# BatteryBalancer.net
KiCad netlist of a schematic drawn in EAGLE
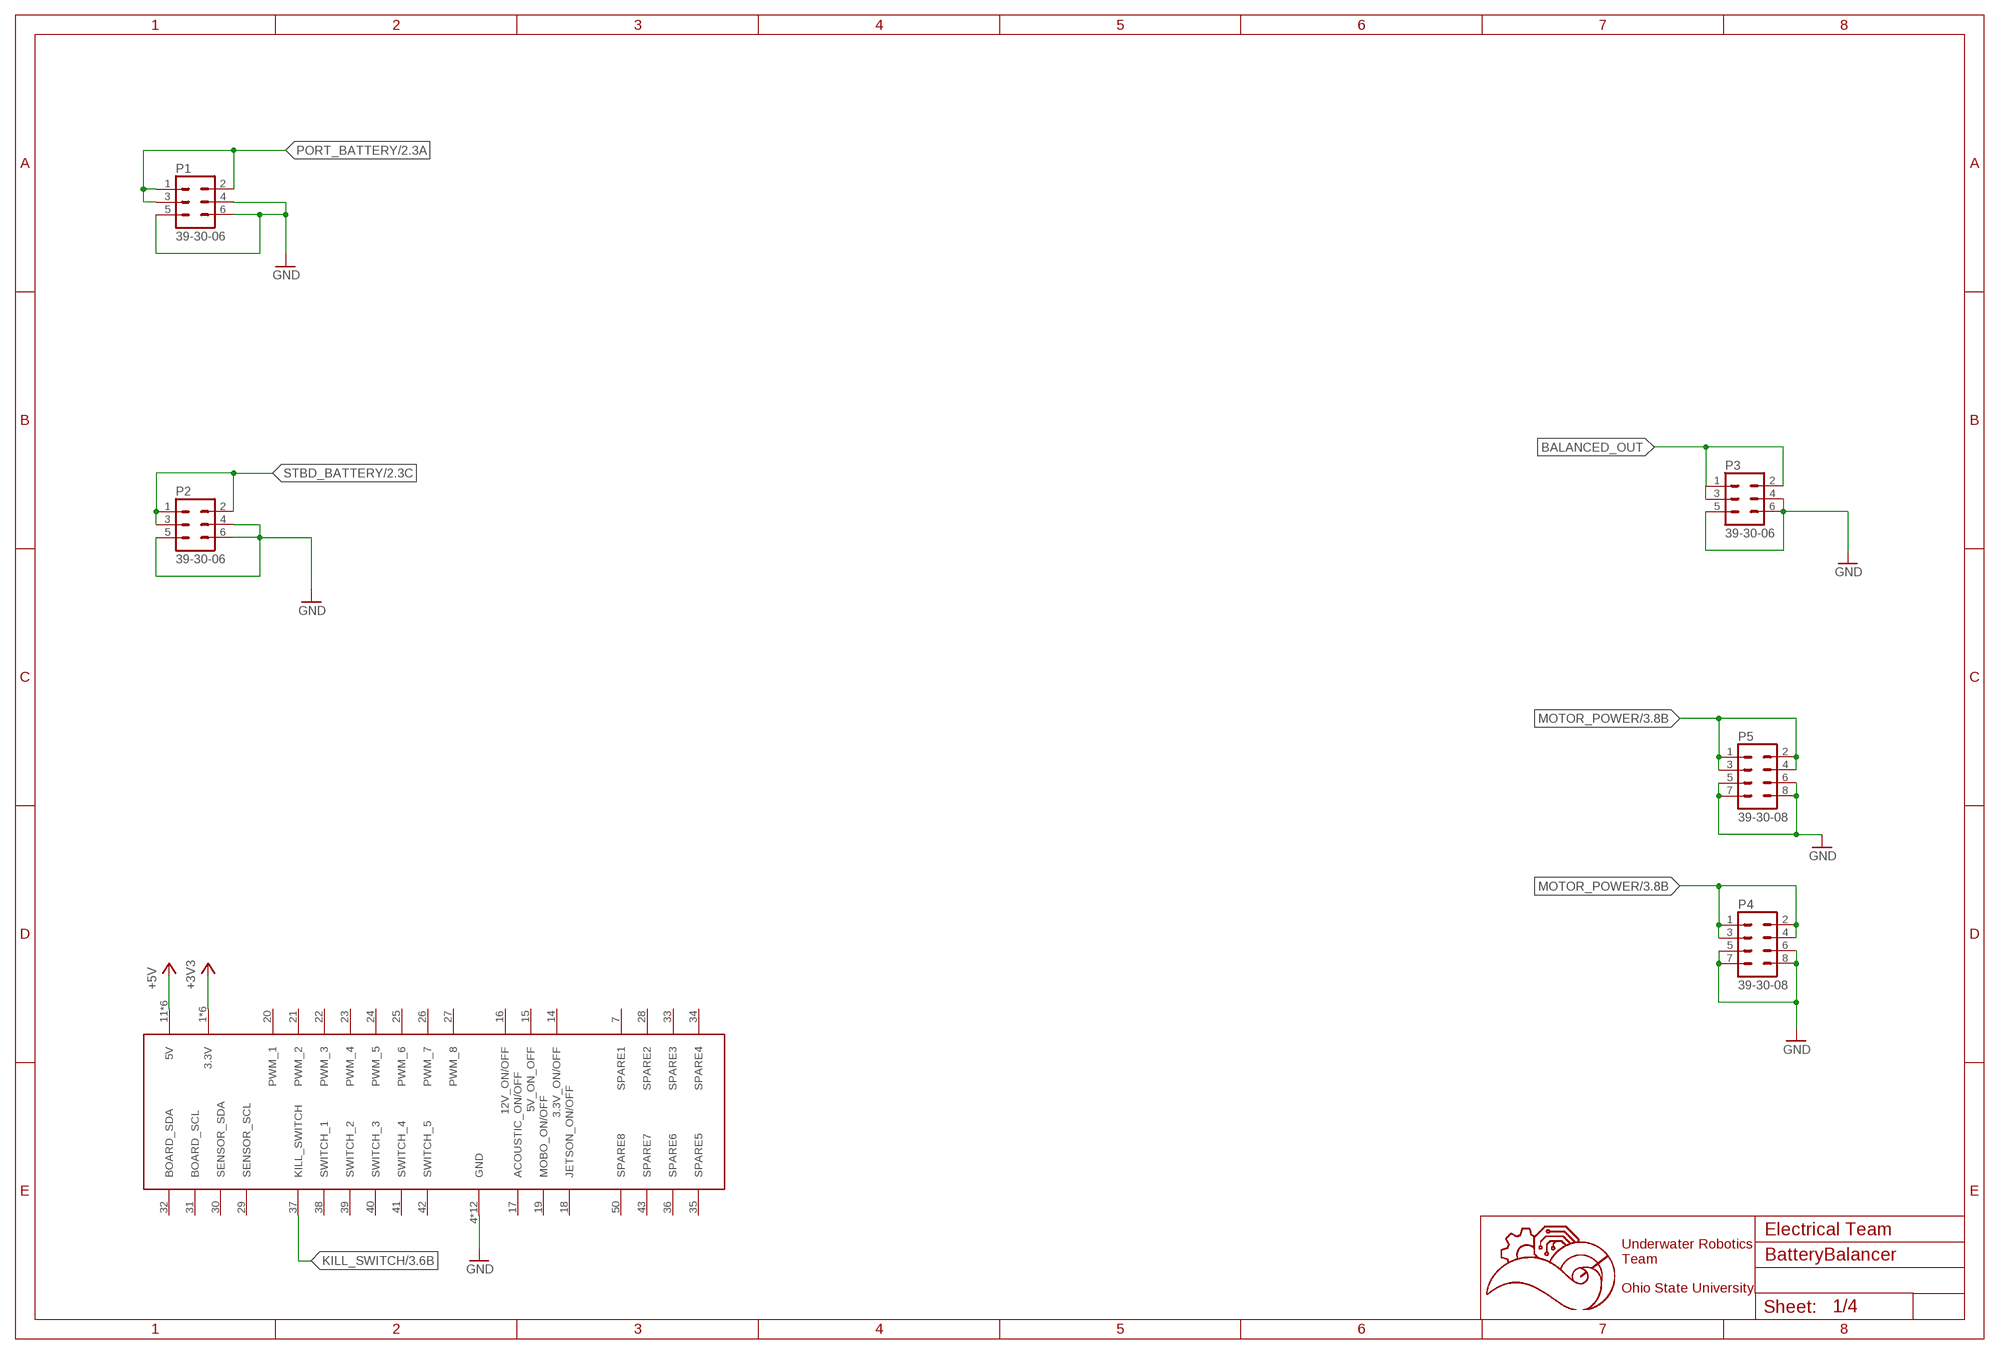
[diagram p0: schematic, sheet 1]
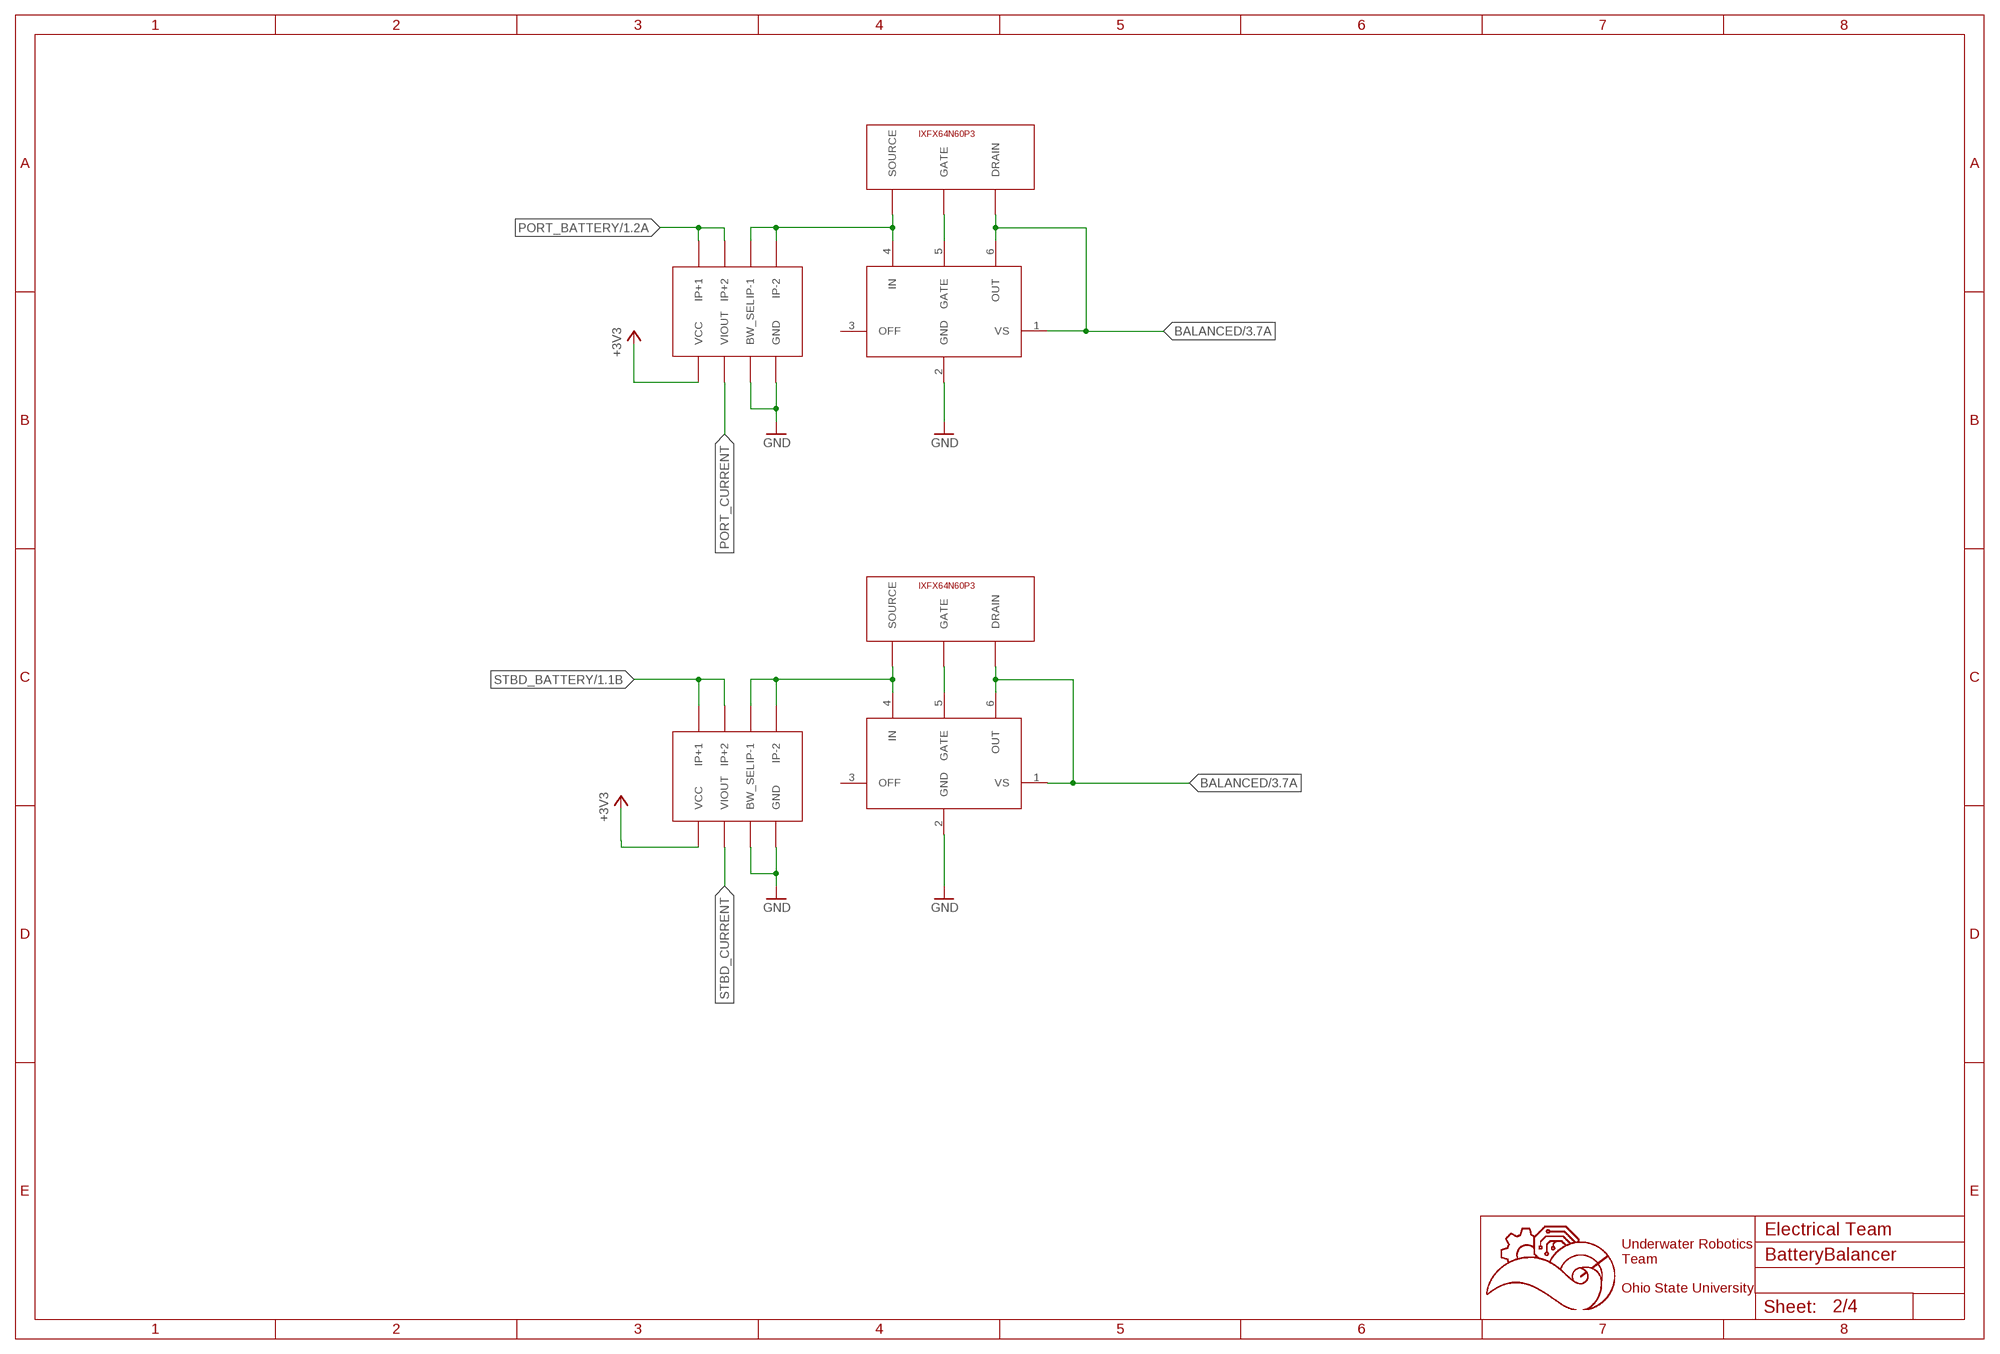
[diagram p1: schematic, sheet 2]
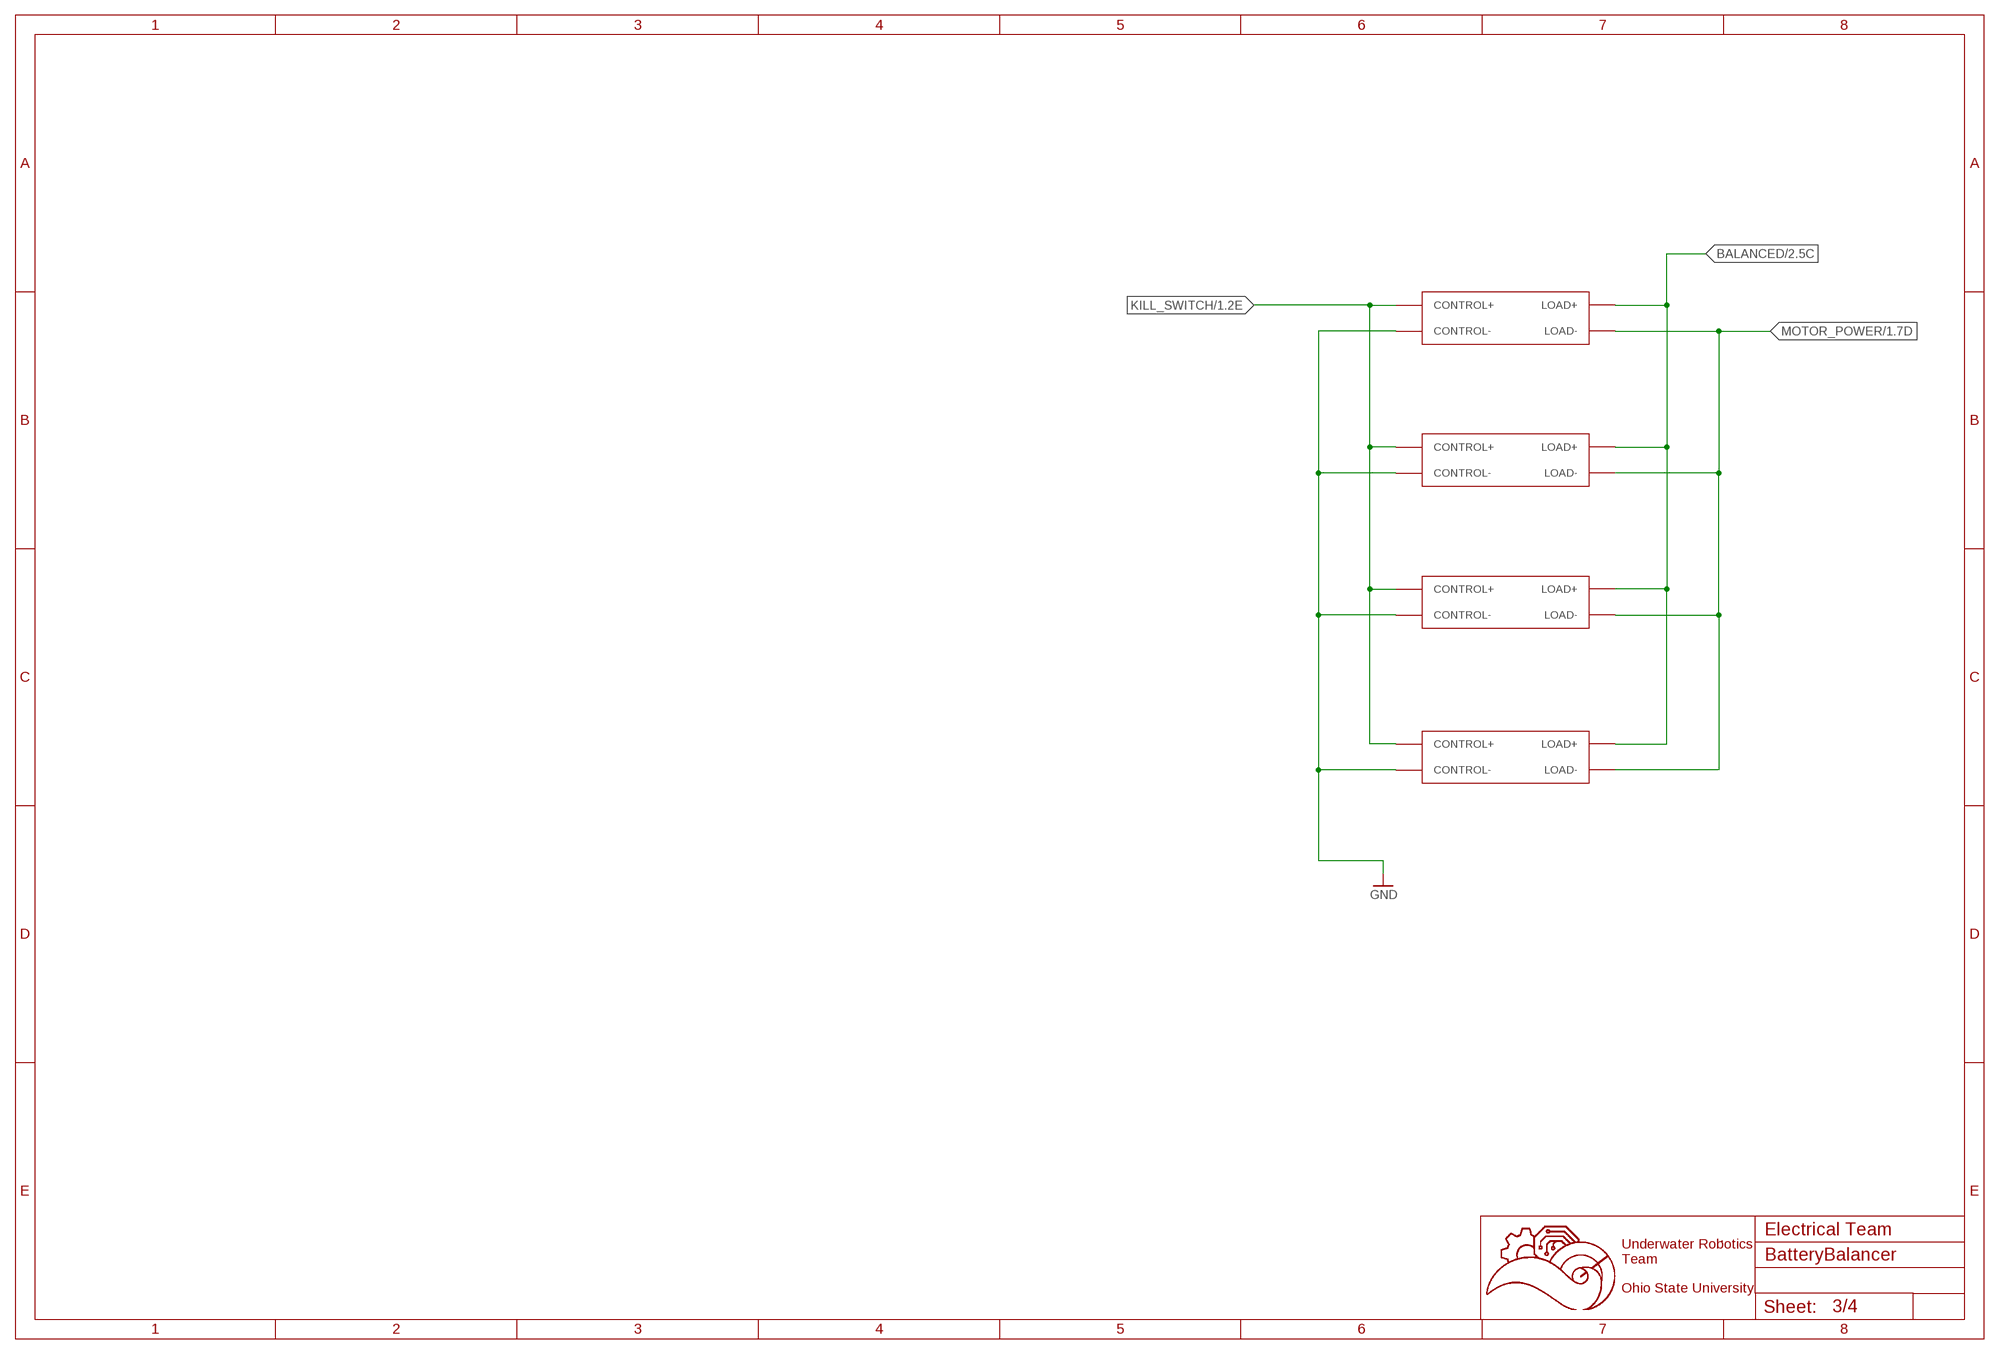
[diagram p2: schematic, sheet 3]
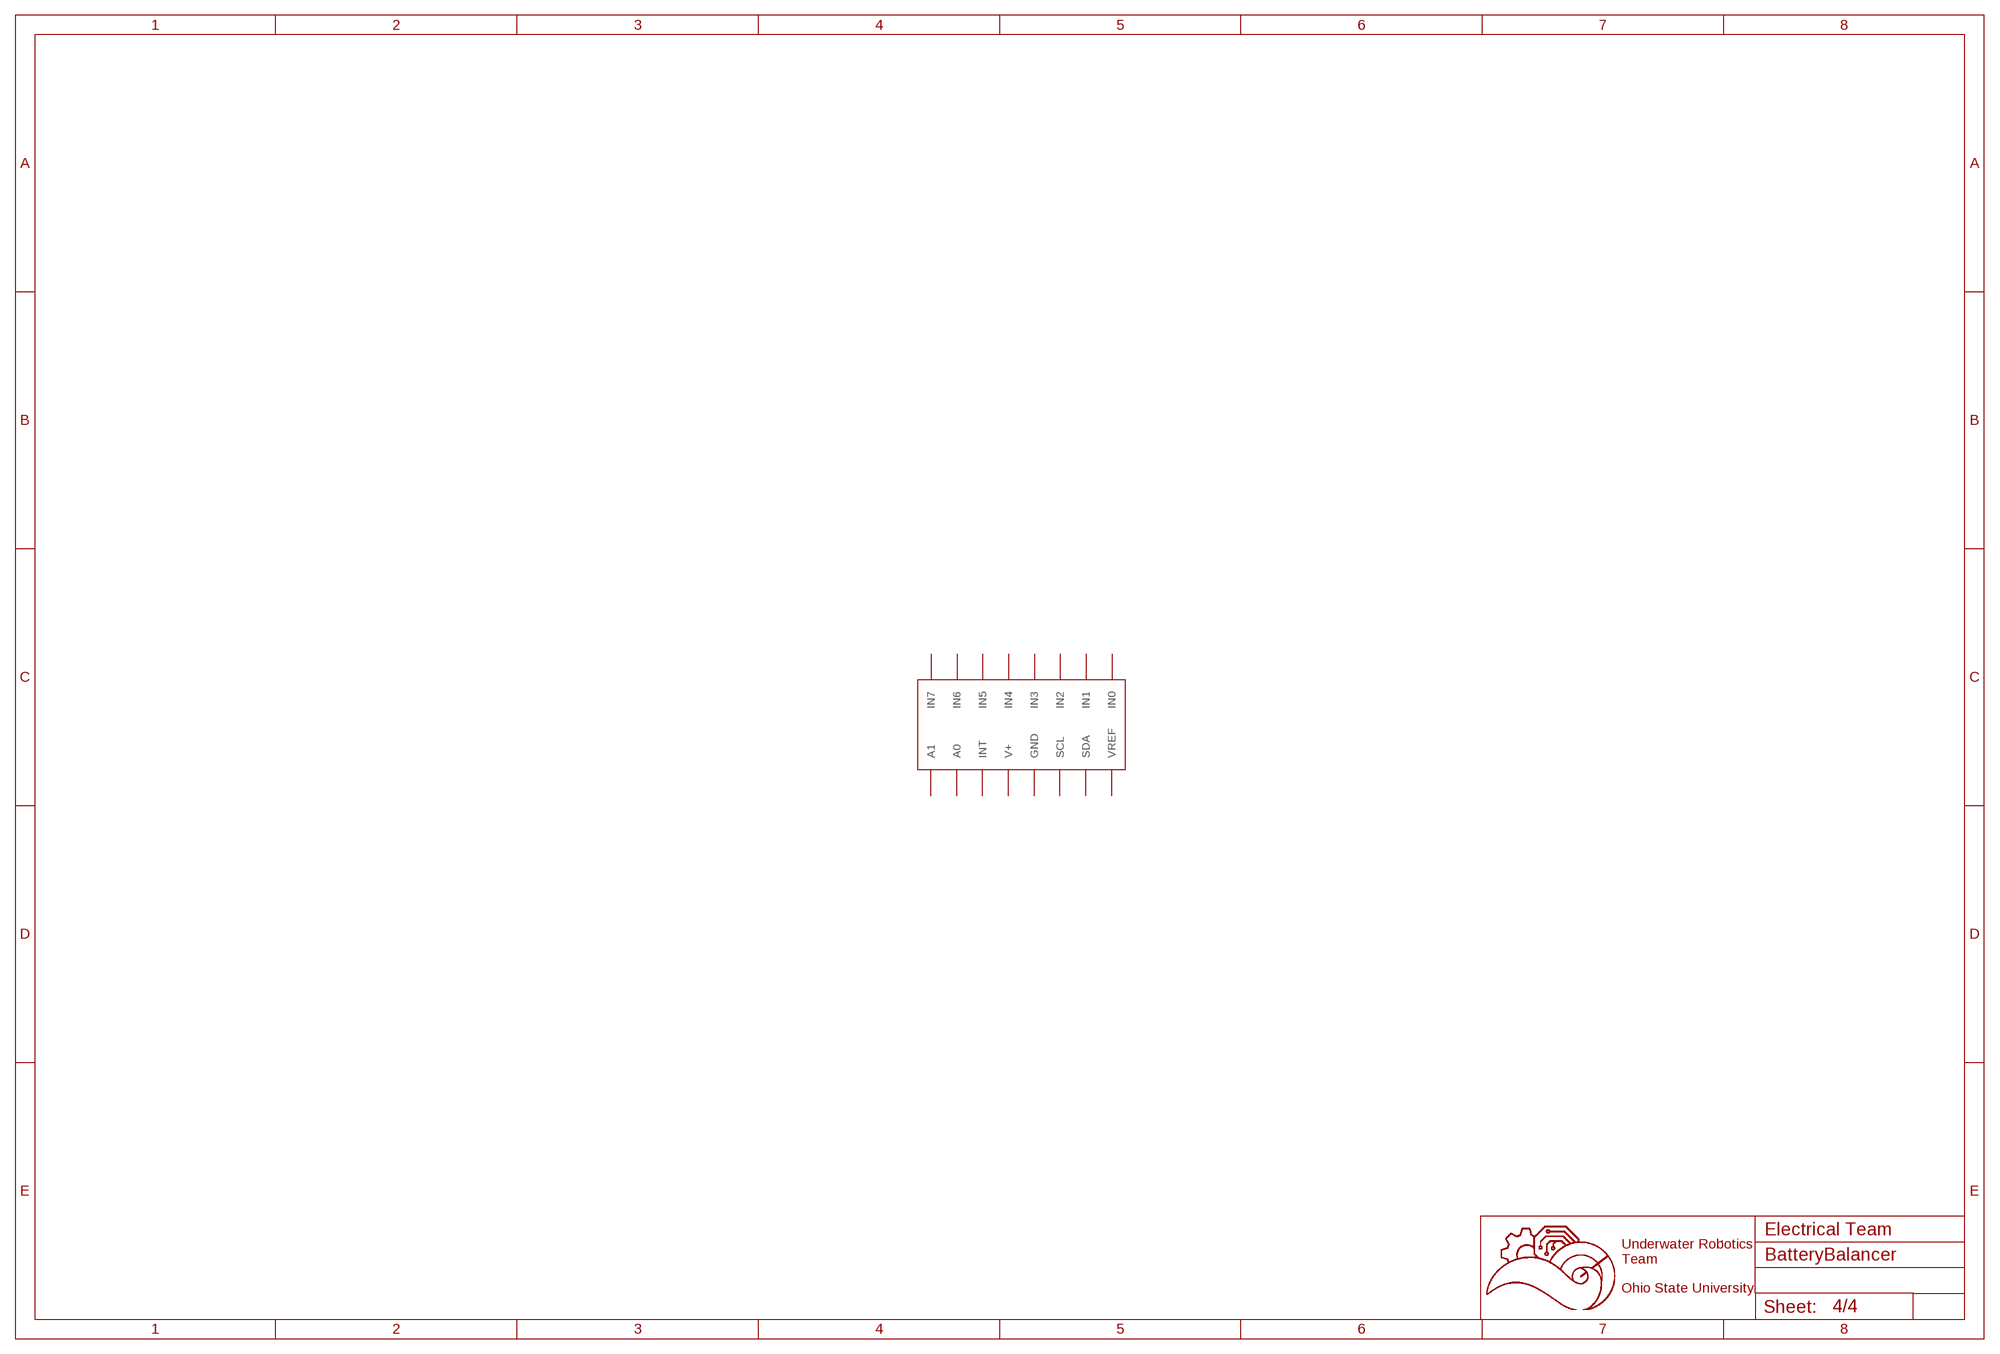
[diagram p3: schematic, sheet 4]

(export (version "E")
  (design (tool "Eeschema 10.0.6"))
  (components
    (comp (ref "U$12")
      (value "ADC128D818")
      (footprint "eagle-import:TSSOP-16")
      (libsource (lib "eagle-import") (part "ADC128D818"))
    )
    (comp (ref "U$8")
      (value "CMX60D20")
      (footprint "eagle-import:CMX60D20")
      (libsource (lib "eagle-import") (part "CMX60D20"))
    )
    (comp (ref "U$9")
      (value "CMX60D20")
      (footprint "eagle-import:CMX60D20")
      (libsource (lib "eagle-import") (part "CMX60D20"))
    )
    (comp (ref "U$10")
      (value "CMX60D20")
      (footprint "eagle-import:CMX60D20")
      (libsource (lib "eagle-import") (part "CMX60D20"))
    )
    (comp (ref "U$11")
      (value "CMX60D20")
      (footprint "eagle-import:CMX60D20")
      (libsource (lib "eagle-import") (part "CMX60D20"))
    )
    (comp (ref "U$2")
      (value "LM5050")
      (footprint "eagle-import:LM5050")
      (libsource (lib "eagle-import") (part "LM5050"))
    )
    (comp (ref "U$3")
      (value "LM5050")
      (footprint "eagle-import:LM5050")
      (libsource (lib "eagle-import") (part "LM5050"))
    )
    (comp (ref "U$4")
      (value "IXFX64N60P3")
      (footprint "eagle-import:IXFX64N60P3")
      (libsource (lib "eagle-import") (part "IXFX64N60P3"))
    )
    (comp (ref "U$5")
      (value "IXFX64N60P3")
      (footprint "eagle-import:IXFX64N60P3")
      (libsource (lib "eagle-import") (part "IXFX64N60P3"))
    )
    (comp (ref "U$6")
      (value "ACS722")
      (footprint "eagle-import:SOIC-8")
      (libsource (lib "eagle-import") (part "ACS722"))
    )
    (comp (ref "U$7")
      (value "ACS722")
      (footprint "eagle-import:SOIC-8")
      (libsource (lib "eagle-import") (part "ACS722"))
    )
    (comp (ref "P1")
      (value "39-30-06")
      (footprint "eagle-import:39-30-_06_")
      (libsource (lib "eagle-import") (part "39-30-?06?"))
    )
    (comp (ref "P2")
      (value "39-30-06")
      (footprint "eagle-import:39-30-_06_")
      (libsource (lib "eagle-import") (part "39-30-?06?"))
    )
    (comp (ref "P3")
      (value "39-30-06")
      (footprint "eagle-import:39-30-_06_")
      (libsource (lib "eagle-import") (part "39-30-?06?"))
    )
    (comp (ref "P4")
      (value "39-30-08")
      (footprint "eagle-import:39-30-_08_")
      (libsource (lib "eagle-import") (part "39-30-?08?"))
    )
    (comp (ref "P5")
      (value "39-30-08")
      (footprint "eagle-import:39-30-_08_")
      (libsource (lib "eagle-import") (part "39-30-?08?"))
    )
    (comp (ref "U$1")
      (value "5530843-EDGE")
      (footprint "eagle-import:5530843-6-BOARDFINGERS")
      (libsource (lib "eagle-import") (part "5530843-EDGE"))
    )
  )
  (nets
    (net (code "1") (name "+3V3") (class "Default")
      (node (ref "U$1") (pin "1") (pinfunction "3.3V_1") (pintype "bidirectional"))
      (node (ref "U$1") (pin "2") (pinfunction "3.3V_2") (pintype "bidirectional"))
      (node (ref "U$1") (pin "3") (pinfunction "3.3V_3") (pintype "bidirectional"))
      (node (ref "U$1") (pin "54") (pinfunction "3.3V_54") (pintype "bidirectional"))
      (node (ref "U$1") (pin "55") (pinfunction "3.3V_55") (pintype "bidirectional"))
      (node (ref "U$1") (pin "56") (pinfunction "3.3V_56") (pintype "bidirectional"))
      (node (ref "U$6") (pin "VCC") (pinfunction "VCC_VCC") (pintype "bidirectional"))
      (node (ref "U$7") (pin "VCC") (pinfunction "VCC_VCC") (pintype "bidirectional"))
    )
    (net (code "2") (name "+5V") (class "Default")
      (node (ref "U$1") (pin "11") (pinfunction "5V_11") (pintype "bidirectional"))
      (node (ref "U$1") (pin "12") (pinfunction "5V_12") (pintype "bidirectional"))
      (node (ref "U$1") (pin "13") (pinfunction "5V_13") (pintype "bidirectional"))
      (node (ref "U$1") (pin "44") (pinfunction "5V_44") (pintype "bidirectional"))
      (node (ref "U$1") (pin "45") (pinfunction "5V_45") (pintype "bidirectional"))
      (node (ref "U$1") (pin "46") (pinfunction "5V_46") (pintype "bidirectional"))
    )
    (net (code "3") (name "BALANCED") (class "Default")
      (node (ref "U$10") (pin "LOAD+") (pinfunction "LOAD+_LOAD+") (pintype "bidirectional"))
      (node (ref "U$11") (pin "LOAD+") (pinfunction "LOAD+_LOAD+") (pintype "bidirectional"))
      (node (ref "U$2") (pin "1") (pinfunction "VS_1") (pintype "bidirectional"))
      (node (ref "U$2") (pin "6") (pinfunction "OUT_6") (pintype "bidirectional"))
      (node (ref "U$3") (pin "1") (pinfunction "VS_1") (pintype "bidirectional"))
      (node (ref "U$3") (pin "6") (pinfunction "OUT_6") (pintype "bidirectional"))
      (node (ref "U$4") (pin "DRAIN") (pinfunction "DRAIN_DRAIN") (pintype "bidirectional"))
      (node (ref "U$5") (pin "DRAIN") (pinfunction "DRAIN_DRAIN") (pintype "bidirectional"))
      (node (ref "U$8") (pin "LOAD+") (pinfunction "LOAD+_LOAD+") (pintype "bidirectional"))
      (node (ref "U$9") (pin "LOAD+") (pinfunction "LOAD+_LOAD+") (pintype "bidirectional"))
    )
    (net (code "4") (name "BALANCED_OUT") (class "Default")
      (node (ref "P3") (pin "1") (pinfunction "1_1") (pintype "passive"))
      (node (ref "P3") (pin "2") (pinfunction "2_2") (pintype "passive"))
      (node (ref "P3") (pin "3") (pinfunction "3_3") (pintype "passive"))
    )
    (net (code "5") (name "GND") (class "Default")
      (node (ref "P1") (pin "4") (pinfunction "4_4") (pintype "passive"))
      (node (ref "P1") (pin "5") (pinfunction "5_5") (pintype "passive"))
      (node (ref "P1") (pin "6") (pinfunction "6_6") (pintype "passive"))
      (node (ref "P2") (pin "4") (pinfunction "4_4") (pintype "passive"))
      (node (ref "P2") (pin "5") (pinfunction "5_5") (pintype "passive"))
      (node (ref "P2") (pin "6") (pinfunction "6_6") (pintype "passive"))
      (node (ref "P3") (pin "4") (pinfunction "4_4") (pintype "passive"))
      (node (ref "P3") (pin "5") (pinfunction "5_5") (pintype "passive"))
      (node (ref "P3") (pin "6") (pinfunction "6_6") (pintype "passive"))
      (node (ref "P4") (pin "5") (pinfunction "5_5") (pintype "passive"))
      (node (ref "P4") (pin "6") (pinfunction "6_6") (pintype "passive"))
      (node (ref "P4") (pin "7") (pinfunction "7_7") (pintype "passive"))
      (node (ref "P4") (pin "8") (pinfunction "8_8") (pintype "passive"))
      (node (ref "P5") (pin "5") (pinfunction "5_5") (pintype "passive"))
      (node (ref "P5") (pin "6") (pinfunction "6_6") (pintype "passive"))
      (node (ref "P5") (pin "7") (pinfunction "7_7") (pintype "passive"))
      (node (ref "P5") (pin "8") (pinfunction "8_8") (pintype "passive"))
      (node (ref "U$1") (pin "10") (pinfunction "GND_10") (pintype "bidirectional"))
      (node (ref "U$1") (pin "4") (pinfunction "GND_4") (pintype "bidirectional"))
      (node (ref "U$1") (pin "47") (pinfunction "GND_47") (pintype "bidirectional"))
      (node (ref "U$1") (pin "48") (pinfunction "GND_48") (pintype "bidirectional"))
      (node (ref "U$1") (pin "49") (pinfunction "GND_49") (pintype "bidirectional"))
      (node (ref "U$1") (pin "5") (pinfunction "GND_5") (pintype "bidirectional"))
      (node (ref "U$1") (pin "51") (pinfunction "GND_51") (pintype "bidirectional"))
      (node (ref "U$1") (pin "52") (pinfunction "GND_52") (pintype "bidirectional"))
      (node (ref "U$1") (pin "53") (pinfunction "GND_53") (pintype "bidirectional"))
      (node (ref "U$1") (pin "6") (pinfunction "GND_6") (pintype "bidirectional"))
      (node (ref "U$1") (pin "8") (pinfunction "GND_8") (pintype "bidirectional"))
      (node (ref "U$1") (pin "9") (pinfunction "GND_9") (pintype "bidirectional"))
      (node (ref "U$10") (pin "CONTROL-") (pinfunction "CONTROL-_CONTROL-") (pintype "bidirectional"))
      (node (ref "U$11") (pin "CONTROL-") (pinfunction "CONTROL-_CONTROL-") (pintype "bidirectional"))
      (node (ref "U$2") (pin "2") (pinfunction "GND_2") (pintype "bidirectional"))
      (node (ref "U$3") (pin "2") (pinfunction "GND_2") (pintype "bidirectional"))
      (node (ref "U$6") (pin "BW_SEL") (pinfunction "BW_SEL_BW_SEL") (pintype "bidirectional"))
      (node (ref "U$6") (pin "GND") (pinfunction "GND_GND") (pintype "bidirectional"))
      (node (ref "U$7") (pin "BW_SEL") (pinfunction "BW_SEL_BW_SEL") (pintype "bidirectional"))
      (node (ref "U$7") (pin "GND") (pinfunction "GND_GND") (pintype "bidirectional"))
      (node (ref "U$8") (pin "CONTROL-") (pinfunction "CONTROL-_CONTROL-") (pintype "bidirectional"))
      (node (ref "U$9") (pin "CONTROL-") (pinfunction "CONTROL-_CONTROL-") (pintype "bidirectional"))
    )
    (net (code "6") (name "KILL_SWITCH") (class "Default")
      (node (ref "U$1") (pin "37") (pinfunction "KILL_SWITCH_37") (pintype "output"))
      (node (ref "U$10") (pin "CONTROL+") (pinfunction "CONTROL+_CONTROL+") (pintype "bidirectional"))
      (node (ref "U$11") (pin "CONTROL+") (pinfunction "CONTROL+_CONTROL+") (pintype "bidirectional"))
      (node (ref "U$8") (pin "CONTROL+") (pinfunction "CONTROL+_CONTROL+") (pintype "bidirectional"))
      (node (ref "U$9") (pin "CONTROL+") (pinfunction "CONTROL+_CONTROL+") (pintype "bidirectional"))
    )
    (net (code "7") (name "MOTOR_POWER") (class "Default")
      (node (ref "P4") (pin "1") (pinfunction "1_1") (pintype "passive"))
      (node (ref "P4") (pin "2") (pinfunction "2_2") (pintype "passive"))
      (node (ref "P4") (pin "3") (pinfunction "3_3") (pintype "passive"))
      (node (ref "P4") (pin "4") (pinfunction "4_4") (pintype "passive"))
      (node (ref "P5") (pin "1") (pinfunction "1_1") (pintype "passive"))
      (node (ref "P5") (pin "2") (pinfunction "2_2") (pintype "passive"))
      (node (ref "P5") (pin "3") (pinfunction "3_3") (pintype "passive"))
      (node (ref "P5") (pin "4") (pinfunction "4_4") (pintype "passive"))
      (node (ref "U$10") (pin "LOAD-") (pinfunction "LOAD-_LOAD-") (pintype "bidirectional"))
      (node (ref "U$11") (pin "LOAD-") (pinfunction "LOAD-_LOAD-") (pintype "bidirectional"))
      (node (ref "U$8") (pin "LOAD-") (pinfunction "LOAD-_LOAD-") (pintype "bidirectional"))
      (node (ref "U$9") (pin "LOAD-") (pinfunction "LOAD-_LOAD-") (pintype "bidirectional"))
    )
    (net (code "8") (name "Net-(U$2-GATE)") (class "Default")
      (node (ref "U$2") (pin "5") (pinfunction "GATE_5") (pintype "bidirectional"))
      (node (ref "U$4") (pin "GATE") (pinfunction "GATE_GATE") (pintype "bidirectional"))
    )
    (net (code "9") (name "Net-(U$2-IN)") (class "Default")
      (node (ref "U$2") (pin "4") (pinfunction "IN_4") (pintype "bidirectional"))
      (node (ref "U$4") (pin "SOURCE") (pinfunction "SOURCE_SOURCE") (pintype "bidirectional"))
      (node (ref "U$6") (pin "IP-1") (pinfunction "IP-1_IP-1") (pintype "bidirectional"))
      (node (ref "U$6") (pin "IP-2") (pinfunction "IP-2_IP-2") (pintype "bidirectional"))
    )
    (net (code "10") (name "Net-(U$3-GATE)") (class "Default")
      (node (ref "U$3") (pin "5") (pinfunction "GATE_5") (pintype "bidirectional"))
      (node (ref "U$5") (pin "GATE") (pinfunction "GATE_GATE") (pintype "bidirectional"))
    )
    (net (code "11") (name "Net-(U$3-IN)") (class "Default")
      (node (ref "U$3") (pin "4") (pinfunction "IN_4") (pintype "bidirectional"))
      (node (ref "U$5") (pin "SOURCE") (pinfunction "SOURCE_SOURCE") (pintype "bidirectional"))
      (node (ref "U$7") (pin "IP-1") (pinfunction "IP-1_IP-1") (pintype "bidirectional"))
      (node (ref "U$7") (pin "IP-2") (pinfunction "IP-2_IP-2") (pintype "bidirectional"))
    )
    (net (code "12") (name "PORT_BATTERY") (class "Default")
      (node (ref "P1") (pin "1") (pinfunction "1_1") (pintype "passive"))
      (node (ref "P1") (pin "2") (pinfunction "2_2") (pintype "passive"))
      (node (ref "P1") (pin "3") (pinfunction "3_3") (pintype "passive"))
      (node (ref "U$6") (pin "IP+1") (pinfunction "IP+1_IP+1") (pintype "bidirectional"))
      (node (ref "U$6") (pin "IP+2") (pinfunction "IP+2_IP+2") (pintype "bidirectional"))
    )
    (net (code "13") (name "PORT_CURRENT") (class "Default")
      (node (ref "U$6") (pin "VIOUT") (pinfunction "VIOUT_VIOUT") (pintype "bidirectional"))
    )
    (net (code "14") (name "STBD_BATTERY") (class "Default")
      (node (ref "P2") (pin "1") (pinfunction "1_1") (pintype "passive"))
      (node (ref "P2") (pin "2") (pinfunction "2_2") (pintype "passive"))
      (node (ref "P2") (pin "3") (pinfunction "3_3") (pintype "passive"))
      (node (ref "U$7") (pin "IP+1") (pinfunction "IP+1_IP+1") (pintype "bidirectional"))
      (node (ref "U$7") (pin "IP+2") (pinfunction "IP+2_IP+2") (pintype "bidirectional"))
    )
    (net (code "15") (name "STBD_CURRENT") (class "Default")
      (node (ref "U$7") (pin "VIOUT") (pinfunction "VIOUT_VIOUT") (pintype "bidirectional"))
    )
    (net (code "16") (name "unconnected-(U$1-3.3V_ON{slash}OFF-Pad14)") (class "Default")
      (node (ref "U$1") (pin "14") (pinfunction "3.3V_ON/OFF_14") (pintype "bidirectional"))
    )
    (net (code "17") (name "unconnected-(U$1-5V_ON_OFF-Pad15)") (class "Default")
      (node (ref "U$1") (pin "15") (pinfunction "5V_ON_OFF_15") (pintype "bidirectional"))
    )
    (net (code "18") (name "unconnected-(U$1-12V_ON{slash}OFF-Pad16)") (class "Default")
      (node (ref "U$1") (pin "16") (pinfunction "12V_ON/OFF_16") (pintype "bidirectional"))
    )
    (net (code "19") (name "unconnected-(U$1-ACOUSTIC_ON{slash}OFF-Pad17)") (class "Default")
      (node (ref "U$1") (pin "17") (pinfunction "ACOUSTIC_ON/OFF_17") (pintype "bidirectional"))
    )
    (net (code "20") (name "unconnected-(U$1-BOARD_SCL-Pad31)") (class "Default")
      (node (ref "U$1") (pin "31") (pinfunction "BOARD_SCL_31") (pintype "bidirectional"))
    )
    (net (code "21") (name "unconnected-(U$1-BOARD_SDA-Pad32)") (class "Default")
      (node (ref "U$1") (pin "32") (pinfunction "BOARD_SDA_32") (pintype "bidirectional"))
    )
    (net (code "22") (name "unconnected-(U$1-JETSON_ON{slash}OFF-Pad18)") (class "Default")
      (node (ref "U$1") (pin "18") (pinfunction "JETSON_ON/OFF_18") (pintype "bidirectional"))
    )
    (net (code "23") (name "unconnected-(U$1-MOBO_ON{slash}OFF-Pad19)") (class "Default")
      (node (ref "U$1") (pin "19") (pinfunction "MOBO_ON/OFF_19") (pintype "bidirectional"))
    )
    (net (code "24") (name "unconnected-(U$1-PWM_1-Pad20)") (class "Default")
      (node (ref "U$1") (pin "20") (pinfunction "PWM_1_20") (pintype "bidirectional"))
    )
    (net (code "25") (name "unconnected-(U$1-PWM_2-Pad21)") (class "Default")
      (node (ref "U$1") (pin "21") (pinfunction "PWM_2_21") (pintype "bidirectional"))
    )
    (net (code "26") (name "unconnected-(U$1-PWM_3-Pad22)") (class "Default")
      (node (ref "U$1") (pin "22") (pinfunction "PWM_3_22") (pintype "bidirectional"))
    )
    (net (code "27") (name "unconnected-(U$1-PWM_4-Pad23)") (class "Default")
      (node (ref "U$1") (pin "23") (pinfunction "PWM_4_23") (pintype "bidirectional"))
    )
    (net (code "28") (name "unconnected-(U$1-PWM_5-Pad24)") (class "Default")
      (node (ref "U$1") (pin "24") (pinfunction "PWM_5_24") (pintype "bidirectional"))
    )
    (net (code "29") (name "unconnected-(U$1-PWM_6-Pad25)") (class "Default")
      (node (ref "U$1") (pin "25") (pinfunction "PWM_6_25") (pintype "bidirectional"))
    )
    (net (code "30") (name "unconnected-(U$1-PWM_7-Pad26)") (class "Default")
      (node (ref "U$1") (pin "26") (pinfunction "PWM_7_26") (pintype "bidirectional"))
    )
    (net (code "31") (name "unconnected-(U$1-PWM_8-Pad27)") (class "Default")
      (node (ref "U$1") (pin "27") (pinfunction "PWM_8_27") (pintype "bidirectional"))
    )
    (net (code "32") (name "unconnected-(U$1-SENSOR_SCL-Pad29)") (class "Default")
      (node (ref "U$1") (pin "29") (pinfunction "SENSOR_SCL_29") (pintype "bidirectional"))
    )
    (net (code "33") (name "unconnected-(U$1-SENSOR_SDA-Pad30)") (class "Default")
      (node (ref "U$1") (pin "30") (pinfunction "SENSOR_SDA_30") (pintype "bidirectional"))
    )
    (net (code "34") (name "unconnected-(U$1-SPARE1-Pad7)") (class "Default")
      (node (ref "U$1") (pin "7") (pinfunction "SPARE1_7") (pintype "bidirectional"))
    )
    (net (code "35") (name "unconnected-(U$1-SPARE2-Pad28)") (class "Default")
      (node (ref "U$1") (pin "28") (pinfunction "SPARE2_28") (pintype "bidirectional"))
    )
    (net (code "36") (name "unconnected-(U$1-SPARE3-Pad33)") (class "Default")
      (node (ref "U$1") (pin "33") (pinfunction "SPARE3_33") (pintype "bidirectional"))
    )
    (net (code "37") (name "unconnected-(U$1-SPARE4-Pad34)") (class "Default")
      (node (ref "U$1") (pin "34") (pinfunction "SPARE4_34") (pintype "bidirectional"))
    )
    (net (code "38") (name "unconnected-(U$1-SPARE5-Pad35)") (class "Default")
      (node (ref "U$1") (pin "35") (pinfunction "SPARE5_35") (pintype "bidirectional"))
    )
    (net (code "39") (name "unconnected-(U$1-SPARE6-Pad36)") (class "Default")
      (node (ref "U$1") (pin "36") (pinfunction "SPARE6_36") (pintype "bidirectional"))
    )
    (net (code "40") (name "unconnected-(U$1-SPARE7-Pad43)") (class "Default")
      (node (ref "U$1") (pin "43") (pinfunction "SPARE7_43") (pintype "bidirectional"))
    )
    (net (code "41") (name "unconnected-(U$1-SPARE8-Pad50)") (class "Default")
      (node (ref "U$1") (pin "50") (pinfunction "SPARE8_50") (pintype "bidirectional"))
    )
    (net (code "42") (name "unconnected-(U$1-SWITCH_1-Pad38)") (class "Default")
      (node (ref "U$1") (pin "38") (pinfunction "SWITCH_1_38") (pintype "output"))
    )
    (net (code "43") (name "unconnected-(U$1-SWITCH_2-Pad39)") (class "Default")
      (node (ref "U$1") (pin "39") (pinfunction "SWITCH_2_39") (pintype "output"))
    )
    (net (code "44") (name "unconnected-(U$1-SWITCH_3-Pad40)") (class "Default")
      (node (ref "U$1") (pin "40") (pinfunction "SWITCH_3_40") (pintype "output"))
    )
    (net (code "45") (name "unconnected-(U$1-SWITCH_4-Pad41)") (class "Default")
      (node (ref "U$1") (pin "41") (pinfunction "SWITCH_4_41") (pintype "output"))
    )
    (net (code "46") (name "unconnected-(U$1-SWITCH_5-Pad42)") (class "Default")
      (node (ref "U$1") (pin "42") (pinfunction "SWITCH_5_42") (pintype "output"))
    )
    (net (code "47") (name "unconnected-(U$2-OFF-Pad3)") (class "Default")
      (node (ref "U$2") (pin "3") (pinfunction "OFF_3") (pintype "bidirectional"))
    )
    (net (code "48") (name "unconnected-(U$3-OFF-Pad3)") (class "Default")
      (node (ref "U$3") (pin "3") (pinfunction "OFF_3") (pintype "bidirectional"))
    )
    (net (code "49") (name "unconnected-(U$12-PadA0)") (class "Default")
      (node (ref "U$12") (pin "A0") (pinfunction "A0_A0") (pintype "bidirectional"))
    )
    (net (code "50") (name "unconnected-(U$12-PadA1)") (class "Default")
      (node (ref "U$12") (pin "A1") (pinfunction "A1_A1") (pintype "bidirectional"))
    )
    (net (code "51") (name "unconnected-(U$12-PadGND)") (class "Default")
      (node (ref "U$12") (pin "GND") (pinfunction "GND_GND") (pintype "bidirectional"))
    )
    (net (code "52") (name "unconnected-(U$12-PadIN0)") (class "Default")
      (node (ref "U$12") (pin "IN0") (pinfunction "IN0_IN0") (pintype "bidirectional"))
    )
    (net (code "53") (name "unconnected-(U$12-PadIN1)") (class "Default")
      (node (ref "U$12") (pin "IN1") (pinfunction "IN1_IN1") (pintype "bidirectional"))
    )
    (net (code "54") (name "unconnected-(U$12-PadIN2)") (class "Default")
      (node (ref "U$12") (pin "IN2") (pinfunction "IN2_IN2") (pintype "bidirectional"))
    )
    (net (code "55") (name "unconnected-(U$12-PadIN3)") (class "Default")
      (node (ref "U$12") (pin "IN3") (pinfunction "IN3_IN3") (pintype "bidirectional"))
    )
    (net (code "56") (name "unconnected-(U$12-PadIN4)") (class "Default")
      (node (ref "U$12") (pin "IN4") (pinfunction "IN4_IN4") (pintype "bidirectional"))
    )
    (net (code "57") (name "unconnected-(U$12-PadIN5)") (class "Default")
      (node (ref "U$12") (pin "IN5") (pinfunction "IN5_IN5") (pintype "bidirectional"))
    )
    (net (code "58") (name "unconnected-(U$12-PadIN6)") (class "Default")
      (node (ref "U$12") (pin "IN6") (pinfunction "IN6_IN6") (pintype "bidirectional"))
    )
    (net (code "59") (name "unconnected-(U$12-PadIN7)") (class "Default")
      (node (ref "U$12") (pin "IN7") (pinfunction "IN7_IN7") (pintype "bidirectional"))
    )
    (net (code "60") (name "unconnected-(U$12-PadINT)") (class "Default")
      (node (ref "U$12") (pin "INT") (pinfunction "INT_INT") (pintype "bidirectional"))
    )
    (net (code "61") (name "unconnected-(U$12-PadSCL)") (class "Default")
      (node (ref "U$12") (pin "SCL") (pinfunction "SCL_SCL") (pintype "bidirectional"))
    )
    (net (code "62") (name "unconnected-(U$12-PadSDA)") (class "Default")
      (node (ref "U$12") (pin "SDA") (pinfunction "SDA_SDA") (pintype "bidirectional"))
    )
    (net (code "63") (name "unconnected-(U$12-PadV+)") (class "Default")
      (node (ref "U$12") (pin "V+") (pinfunction "V+_V+") (pintype "bidirectional"))
    )
    (net (code "64") (name "unconnected-(U$12-PadVREF)") (class "Default")
      (node (ref "U$12") (pin "VREF") (pinfunction "VREF_VREF") (pintype "bidirectional"))
    )
  )
)
